# PuggleBOB.net
KiCad netlist of a schematic drawn in EAGLE
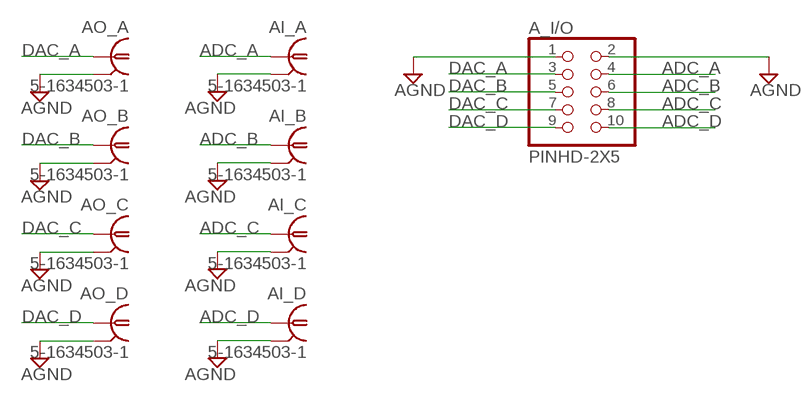
[diagram p0: schematic, sheet 1]

(export (version "E")
  (design (tool "Eeschema 10.0.6"))
  (components
    (comp (ref "AI_A")
      (value "5-1634503-1")
      (footprint "eagle-import:B35N61")
      (libsource (lib "eagle-import") (part "BN35N61"))
    )
    (comp (ref "AI_B")
      (value "5-1634503-1")
      (footprint "eagle-import:B35N61")
      (libsource (lib "eagle-import") (part "BN35N61"))
    )
    (comp (ref "AI_C")
      (value "5-1634503-1")
      (footprint "eagle-import:B35N61")
      (libsource (lib "eagle-import") (part "BN35N61"))
    )
    (comp (ref "AI_D")
      (value "5-1634503-1")
      (footprint "eagle-import:B35N61")
      (libsource (lib "eagle-import") (part "BN35N61"))
    )
    (comp (ref "AO_A")
      (value "5-1634503-1")
      (footprint "eagle-import:B35N61")
      (libsource (lib "eagle-import") (part "BN35N61"))
    )
    (comp (ref "AO_B")
      (value "5-1634503-1")
      (footprint "eagle-import:B35N61")
      (libsource (lib "eagle-import") (part "BN35N61"))
    )
    (comp (ref "AO_C")
      (value "5-1634503-1")
      (footprint "eagle-import:B35N61")
      (libsource (lib "eagle-import") (part "BN35N61"))
    )
    (comp (ref "AO_D")
      (value "5-1634503-1")
      (footprint "eagle-import:B35N61")
      (libsource (lib "eagle-import") (part "BN35N61"))
    )
    (comp (ref "A_I/O")
      (value "PINHD-2X5")
      (footprint "eagle-import:2X05")
      (libsource (lib "eagle-import") (part "PINHD-2X5"))
    )
  )
  (nets
    (net (code "1") (name "/ADC_A") (class "Default")
      (node (ref "AI_A") (pin "1") (pinfunction "1_1") (pintype "passive"))
      (node (ref "A_I/O") (pin "4") (pinfunction "4_4") (pintype "passive"))
    )
    (net (code "2") (name "/ADC_B") (class "Default")
      (node (ref "AI_B") (pin "1") (pinfunction "1_1") (pintype "passive"))
      (node (ref "A_I/O") (pin "6") (pinfunction "6_6") (pintype "passive"))
    )
    (net (code "3") (name "/ADC_C") (class "Default")
      (node (ref "AI_C") (pin "1") (pinfunction "1_1") (pintype "passive"))
      (node (ref "A_I/O") (pin "8") (pinfunction "8_8") (pintype "passive"))
    )
    (net (code "4") (name "/ADC_D") (class "Default")
      (node (ref "AI_D") (pin "1") (pinfunction "1_1") (pintype "passive"))
      (node (ref "A_I/O") (pin "10") (pinfunction "10_10") (pintype "passive"))
    )
    (net (code "5") (name "/DAC_A") (class "Default")
      (node (ref "AO_A") (pin "1") (pinfunction "1_1") (pintype "passive"))
      (node (ref "A_I/O") (pin "3") (pinfunction "3_3") (pintype "passive"))
    )
    (net (code "6") (name "/DAC_B") (class "Default")
      (node (ref "AO_B") (pin "1") (pinfunction "1_1") (pintype "passive"))
      (node (ref "A_I/O") (pin "5") (pinfunction "5_5") (pintype "passive"))
    )
    (net (code "7") (name "/DAC_C") (class "Default")
      (node (ref "AO_C") (pin "1") (pinfunction "1_1") (pintype "passive"))
      (node (ref "A_I/O") (pin "7") (pinfunction "7_7") (pintype "passive"))
    )
    (net (code "8") (name "/DAC_D") (class "Default")
      (node (ref "AO_D") (pin "1") (pinfunction "1_1") (pintype "passive"))
      (node (ref "A_I/O") (pin "9") (pinfunction "9_9") (pintype "passive"))
    )
    (net (code "9") (name "AGND") (class "Default")
      (node (ref "AI_A") (pin "2") (pinfunction "2_2") (pintype "passive"))
      (node (ref "AI_A") (pin "3") (pinfunction "2_3") (pintype "passive"))
      (node (ref "AI_A") (pin "4") (pinfunction "2_4") (pintype "passive"))
      (node (ref "AI_A") (pin "5") (pinfunction "2_5") (pintype "passive"))
      (node (ref "AI_B") (pin "2") (pinfunction "2_2") (pintype "passive"))
      (node (ref "AI_B") (pin "3") (pinfunction "2_3") (pintype "passive"))
      (node (ref "AI_B") (pin "4") (pinfunction "2_4") (pintype "passive"))
      (node (ref "AI_B") (pin "5") (pinfunction "2_5") (pintype "passive"))
      (node (ref "AI_C") (pin "2") (pinfunction "2_2") (pintype "passive"))
      (node (ref "AI_C") (pin "3") (pinfunction "2_3") (pintype "passive"))
      (node (ref "AI_C") (pin "4") (pinfunction "2_4") (pintype "passive"))
      (node (ref "AI_C") (pin "5") (pinfunction "2_5") (pintype "passive"))
      (node (ref "AI_D") (pin "2") (pinfunction "2_2") (pintype "passive"))
      (node (ref "AI_D") (pin "3") (pinfunction "2_3") (pintype "passive"))
      (node (ref "AI_D") (pin "4") (pinfunction "2_4") (pintype "passive"))
      (node (ref "AI_D") (pin "5") (pinfunction "2_5") (pintype "passive"))
      (node (ref "AO_A") (pin "2") (pinfunction "2_2") (pintype "passive"))
      (node (ref "AO_A") (pin "3") (pinfunction "2_3") (pintype "passive"))
      (node (ref "AO_A") (pin "4") (pinfunction "2_4") (pintype "passive"))
      (node (ref "AO_A") (pin "5") (pinfunction "2_5") (pintype "passive"))
      (node (ref "AO_B") (pin "2") (pinfunction "2_2") (pintype "passive"))
      (node (ref "AO_B") (pin "3") (pinfunction "2_3") (pintype "passive"))
      (node (ref "AO_B") (pin "4") (pinfunction "2_4") (pintype "passive"))
      (node (ref "AO_B") (pin "5") (pinfunction "2_5") (pintype "passive"))
      (node (ref "AO_C") (pin "2") (pinfunction "2_2") (pintype "passive"))
      (node (ref "AO_C") (pin "3") (pinfunction "2_3") (pintype "passive"))
      (node (ref "AO_C") (pin "4") (pinfunction "2_4") (pintype "passive"))
      (node (ref "AO_C") (pin "5") (pinfunction "2_5") (pintype "passive"))
      (node (ref "AO_D") (pin "2") (pinfunction "2_2") (pintype "passive"))
      (node (ref "AO_D") (pin "3") (pinfunction "2_3") (pintype "passive"))
      (node (ref "AO_D") (pin "4") (pinfunction "2_4") (pintype "passive"))
      (node (ref "AO_D") (pin "5") (pinfunction "2_5") (pintype "passive"))
      (node (ref "A_I/O") (pin "1") (pinfunction "1_1") (pintype "passive"))
      (node (ref "A_I/O") (pin "2") (pinfunction "2_2") (pintype "passive"))
    )
  )
)
